# SolenoidBoard.net
KiCad netlist of a schematic drawn in EAGLE
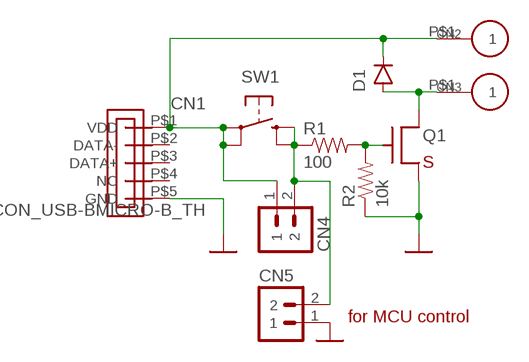
[diagram p0: schematic, sheet 1]

(export (version "E")
  (design (tool "Eeschema 10.0.6"))
  (components
    (comp (ref "CN1")
      (value "CON_USB-BMICRO-B_TH")
      (footprint "eagle-import:USB-MICROB-TH")
      (libsource (lib "eagle-import") (part "CON_USB-BMICRO-B_TH"))
    )
    (comp (ref "CN2")
      (value "CON_P01TH09MM")
      (footprint "eagle-import:PAD_TH09MM")
      (libsource (lib "eagle-import") (part "CON_P01TH09MM"))
    )
    (comp (ref "CN3")
      (value "CON_P01TH09MM")
      (footprint "eagle-import:PAD_TH09MM")
      (libsource (lib "eagle-import") (part "CON_P01TH09MM"))
    )
    (comp (ref "CN4")
      (value "CON_PINHD-1X290")
      (footprint "eagle-import:1X02_90")
      (libsource (lib "eagle-import") (part "CON_PINHD-1X290"))
    )
    (comp (ref "CN5")
      (value "CON_PINHD-1X2PTH")
      (footprint "eagle-import:SPARKFUN_1X02")
      (libsource (lib "eagle-import") (part "CON_PINHD-1X2PTH"))
    )
    (comp (ref "D1")
      (value "DIODESOD123FL")
      (footprint "eagle-import:SOD123FL")
      (libsource (lib "eagle-import") (part "DIODESOD123FL"))
    )
    (comp (ref "Q1")
      (value "TR_NMOS_IRLML6344")
      (footprint "eagle-import:SOT-23-3-2916")
      (libsource (lib "eagle-import") (part "TR_NMOS_IRLML6344"))
    )
    (comp (ref "R1")
      (value "100")
      (footprint "eagle-import:0603")
      (libsource (lib "eagle-import") (part "RES0603"))
    )
    (comp (ref "R2")
      (value "10k")
      (footprint "eagle-import:0603")
      (libsource (lib "eagle-import") (part "RES0603"))
    )
    (comp (ref "SW1")
      (value "SW_TACTSMD_B3FS")
      (footprint "eagle-import:SW_B3FS-1")
      (libsource (lib "eagle-import") (part "SW_TACTSMD_B3FS"))
    )
  )
  (nets
    (net (code "1") (name "Net-(CN1-VDD)") (class "Default")
      (node (ref "CN1") (pin "P$1") (pinfunction "VDD_P$1") (pintype "power_in"))
      (node (ref "CN2") (pin "P$1") (pinfunction "1_P$1") (pintype "bidirectional"))
      (node (ref "CN4") (pin "1") (pinfunction "1_1") (pintype "passive"))
      (node (ref "D1") (pin "P$K") (pinfunction "P$K_P$K") (pintype "bidirectional"))
      (node (ref "SW1") (pin "P$1") (pinfunction "P_P$1") (pintype "passive"))
      (node (ref "SW1") (pin "P$2") (pinfunction "P1_P$2") (pintype "passive"))
    )
    (net (code "2") (name "Net-(CN3-1)") (class "Default")
      (node (ref "CN3") (pin "P$1") (pinfunction "1_P$1") (pintype "bidirectional"))
      (node (ref "D1") (pin "P$A") (pinfunction "P$A_P$A") (pintype "bidirectional"))
      (node (ref "Q1") (pin "3") (pinfunction "D_3") (pintype "bidirectional"))
    )
    (net (code "3") (name "Net-(Q1-G)") (class "Default")
      (node (ref "Q1") (pin "1") (pinfunction "G_1") (pintype "bidirectional"))
      (node (ref "R1") (pin "2") (pinfunction "2_2") (pintype "passive"))
      (node (ref "R2") (pin "2") (pinfunction "2_2") (pintype "passive"))
    )
    (net (code "4") (name "Net-(SW1-S)") (class "Default")
      (node (ref "CN4") (pin "2") (pinfunction "2_2") (pintype "passive"))
      (node (ref "CN5") (pin "2") (pinfunction "2_2") (pintype "passive"))
      (node (ref "R1") (pin "1") (pinfunction "1_1") (pintype "passive"))
      (node (ref "SW1") (pin "P$3") (pinfunction "S_P$3") (pintype "passive"))
      (node (ref "SW1") (pin "P$4") (pinfunction "S1_P$4") (pintype "passive"))
    )
    (net (code "5") (name "POW_GND") (class "Default")
      (node (ref "CN1") (pin "P$5") (pinfunction "GND_P$5") (pintype "power_in"))
      (node (ref "CN5") (pin "1") (pinfunction "1_1") (pintype "passive"))
      (node (ref "Q1") (pin "2") (pinfunction "S_2") (pintype "bidirectional"))
      (node (ref "R2") (pin "1") (pinfunction "1_1") (pintype "passive"))
    )
    (net (code "6") (name "unconnected-(CN1-DATA+-PadP$3)") (class "Default")
      (node (ref "CN1") (pin "P$3") (pinfunction "DATA+_P$3") (pintype "bidirectional"))
    )
    (net (code "7") (name "unconnected-(CN1-DATA--PadP$2)") (class "Default")
      (node (ref "CN1") (pin "P$2") (pinfunction "DATA-_P$2") (pintype "bidirectional"))
    )
    (net (code "8") (name "unconnected-(CN1-NC-PadP$4)") (class "Default")
      (node (ref "CN1") (pin "P$4") (pinfunction "NC_P$4") (pintype "bidirectional"))
    )
  )
)
